# Simple_switch_scale.net
KiCad netlist of a schematic drawn in EAGLE
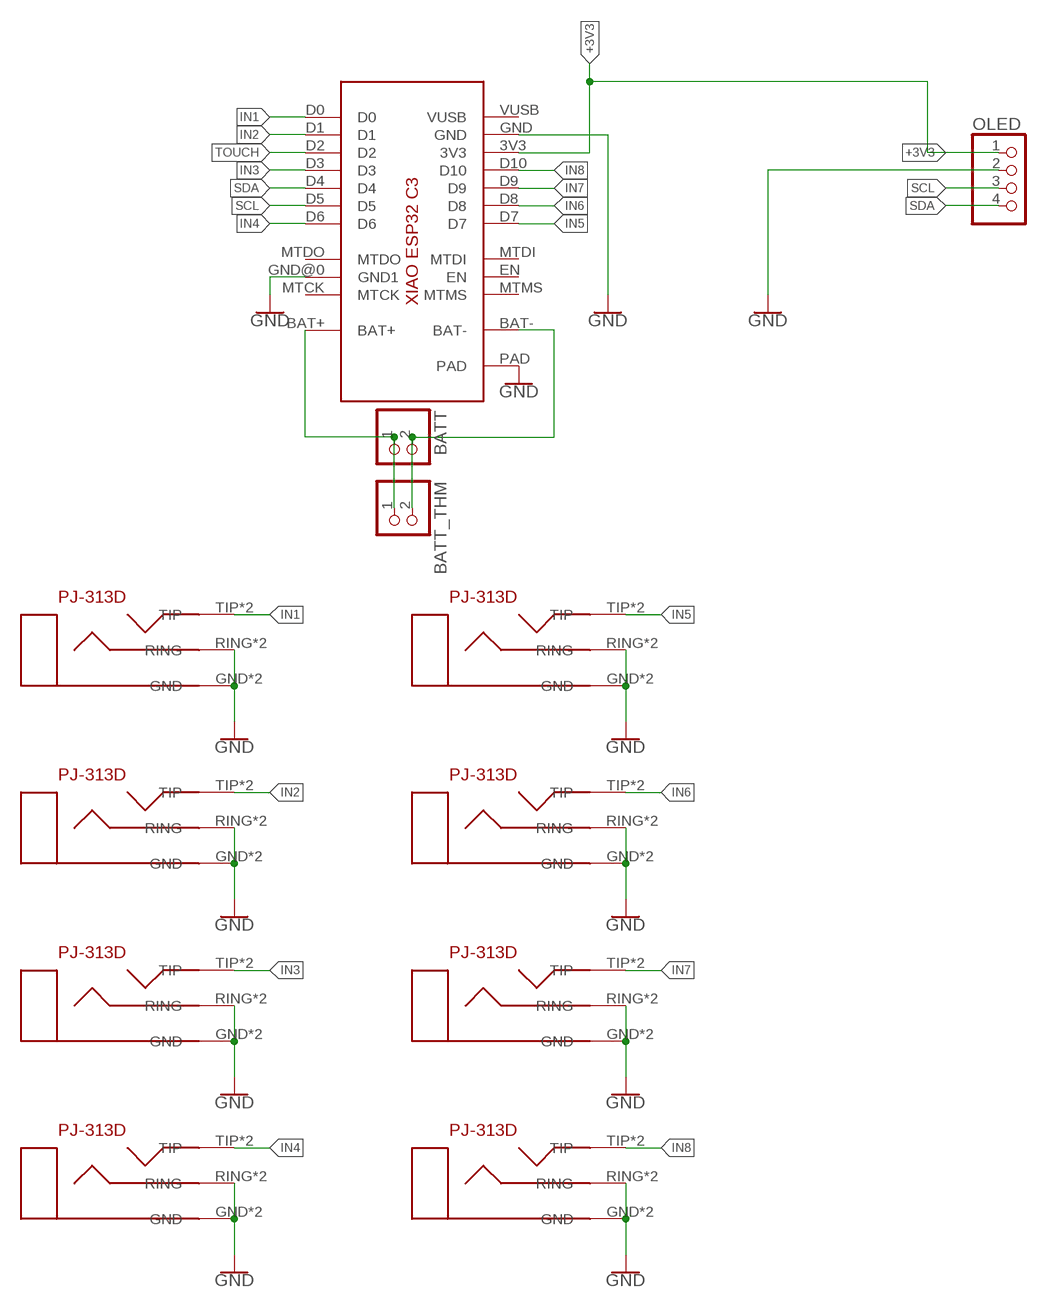
[diagram p0: schematic, sheet 1]

(export (version "E")
  (design (tool "Eeschema 10.0.6"))
  (components
    (comp (ref "BATT")
      (value "JST_2PIN-SMT-RA")
      (footprint "eagle-import:JST-PH-2-SMT-RA")
      (libsource (lib "eagle-import") (part "JST_2PIN-SMT-RA"))
    )
    (comp (ref "BATT_THM")
      (value "JST_2PIN-THM-RA")
      (footprint "eagle-import:JST-PH-2-THM-RA")
      (libsource (lib "eagle-import") (part "JST_2PIN-THM-RA"))
    )
    (comp (ref "IN1")
      (value "3.5MM_JACK")
      (footprint "eagle-import:PJ-313D-SMT")
      (libsource (lib "eagle-import") (part "3.5MM_JACK"))
    )
    (comp (ref "IN2")
      (value "3.5MM_JACK")
      (footprint "eagle-import:PJ-313D-SMT")
      (libsource (lib "eagle-import") (part "3.5MM_JACK"))
    )
    (comp (ref "IN3")
      (value "3.5MM_JACK")
      (footprint "eagle-import:PJ-313D-SMT")
      (libsource (lib "eagle-import") (part "3.5MM_JACK"))
    )
    (comp (ref "IN4")
      (value "3.5MM_JACK")
      (footprint "eagle-import:PJ-313D-SMT")
      (libsource (lib "eagle-import") (part "3.5MM_JACK"))
    )
    (comp (ref "IN5")
      (value "3.5MM_JACK")
      (footprint "eagle-import:PJ-313D-SMT")
      (libsource (lib "eagle-import") (part "3.5MM_JACK"))
    )
    (comp (ref "IN6")
      (value "3.5MM_JACK")
      (footprint "eagle-import:PJ-313D-SMT")
      (libsource (lib "eagle-import") (part "3.5MM_JACK"))
    )
    (comp (ref "IN7")
      (value "3.5MM_JACK")
      (footprint "eagle-import:PJ-313D-SMT")
      (libsource (lib "eagle-import") (part "3.5MM_JACK"))
    )
    (comp (ref "IN8")
      (value "3.5MM_JACK")
      (footprint "eagle-import:PJ-313D-SMT")
      (libsource (lib "eagle-import") (part "3.5MM_JACK"))
    )
    (comp (ref "OLED")
      (value "HEADER-1X4")
      (footprint "eagle-import:1X04_OVAL")
      (libsource (lib "eagle-import") (part "HEADER-1X4"))
    )
    (comp (ref "U$1")
      (value "XIAO_ESP32C3_SMD")
      (footprint "eagle-import:XIAO_ESP32C3_SMD")
      (libsource (lib "eagle-import") (part "XIAO_ESP32C3_SMD"))
    )
  )
  (nets
    (net (code "1") (name "+3V3") (class "Default")
      (node (ref "OLED") (pin "1") (pinfunction "1_1") (pintype "passive"))
      (node (ref "U$1") (pin "3V3") (pinfunction "3V3_3V3") (pintype "bidirectional"))
    )
    (net (code "2") (name "GND") (class "Default")
      (node (ref "IN1") (pin "GND") (pinfunction "GND_GND") (pintype "bidirectional"))
      (node (ref "IN1") (pin "GND0") (pinfunction "GND_GND0") (pintype "bidirectional"))
      (node (ref "IN1") (pin "RING") (pinfunction "RING_RING") (pintype "bidirectional"))
      (node (ref "IN1") (pin "RING0") (pinfunction "RING_RING0") (pintype "bidirectional"))
      (node (ref "IN2") (pin "GND") (pinfunction "GND_GND") (pintype "bidirectional"))
      (node (ref "IN2") (pin "GND0") (pinfunction "GND_GND0") (pintype "bidirectional"))
      (node (ref "IN2") (pin "RING") (pinfunction "RING_RING") (pintype "bidirectional"))
      (node (ref "IN2") (pin "RING0") (pinfunction "RING_RING0") (pintype "bidirectional"))
      (node (ref "IN3") (pin "GND") (pinfunction "GND_GND") (pintype "bidirectional"))
      (node (ref "IN3") (pin "GND0") (pinfunction "GND_GND0") (pintype "bidirectional"))
      (node (ref "IN3") (pin "RING") (pinfunction "RING_RING") (pintype "bidirectional"))
      (node (ref "IN3") (pin "RING0") (pinfunction "RING_RING0") (pintype "bidirectional"))
      (node (ref "IN4") (pin "GND") (pinfunction "GND_GND") (pintype "bidirectional"))
      (node (ref "IN4") (pin "GND0") (pinfunction "GND_GND0") (pintype "bidirectional"))
      (node (ref "IN4") (pin "RING") (pinfunction "RING_RING") (pintype "bidirectional"))
      (node (ref "IN4") (pin "RING0") (pinfunction "RING_RING0") (pintype "bidirectional"))
      (node (ref "IN5") (pin "GND") (pinfunction "GND_GND") (pintype "bidirectional"))
      (node (ref "IN5") (pin "GND0") (pinfunction "GND_GND0") (pintype "bidirectional"))
      (node (ref "IN5") (pin "RING") (pinfunction "RING_RING") (pintype "bidirectional"))
      (node (ref "IN5") (pin "RING0") (pinfunction "RING_RING0") (pintype "bidirectional"))
      (node (ref "IN6") (pin "GND") (pinfunction "GND_GND") (pintype "bidirectional"))
      (node (ref "IN6") (pin "GND0") (pinfunction "GND_GND0") (pintype "bidirectional"))
      (node (ref "IN6") (pin "RING") (pinfunction "RING_RING") (pintype "bidirectional"))
      (node (ref "IN6") (pin "RING0") (pinfunction "RING_RING0") (pintype "bidirectional"))
      (node (ref "IN7") (pin "GND") (pinfunction "GND_GND") (pintype "bidirectional"))
      (node (ref "IN7") (pin "GND0") (pinfunction "GND_GND0") (pintype "bidirectional"))
      (node (ref "IN7") (pin "RING") (pinfunction "RING_RING") (pintype "bidirectional"))
      (node (ref "IN7") (pin "RING0") (pinfunction "RING_RING0") (pintype "bidirectional"))
      (node (ref "IN8") (pin "GND") (pinfunction "GND_GND") (pintype "bidirectional"))
      (node (ref "IN8") (pin "GND0") (pinfunction "GND_GND0") (pintype "bidirectional"))
      (node (ref "IN8") (pin "RING") (pinfunction "RING_RING") (pintype "bidirectional"))
      (node (ref "IN8") (pin "RING0") (pinfunction "RING_RING0") (pintype "bidirectional"))
      (node (ref "OLED") (pin "2") (pinfunction "2_2") (pintype "passive"))
      (node (ref "U$1") (pin "GND") (pinfunction "GND_GND") (pintype "bidirectional"))
      (node (ref "U$1") (pin "GND@0") (pinfunction "GND1_GND@0") (pintype "bidirectional"))
      (node (ref "U$1") (pin "PAD") (pinfunction "PAD_PAD") (pintype "bidirectional"))
    )
    (net (code "3") (name "IN1") (class "Default")
      (node (ref "IN1") (pin "TIP") (pinfunction "TIP_TIP") (pintype "bidirectional"))
      (node (ref "IN1") (pin "TIP0") (pinfunction "TIP_TIP0") (pintype "bidirectional"))
      (node (ref "U$1") (pin "D0") (pinfunction "D0_D0") (pintype "bidirectional"))
    )
    (net (code "4") (name "IN2") (class "Default")
      (node (ref "IN2") (pin "TIP") (pinfunction "TIP_TIP") (pintype "bidirectional"))
      (node (ref "IN2") (pin "TIP0") (pinfunction "TIP_TIP0") (pintype "bidirectional"))
      (node (ref "U$1") (pin "D1") (pinfunction "D1_D1") (pintype "bidirectional"))
    )
    (net (code "5") (name "IN3") (class "Default")
      (node (ref "IN3") (pin "TIP") (pinfunction "TIP_TIP") (pintype "bidirectional"))
      (node (ref "IN3") (pin "TIP0") (pinfunction "TIP_TIP0") (pintype "bidirectional"))
      (node (ref "U$1") (pin "D3") (pinfunction "D3_D3") (pintype "bidirectional"))
    )
    (net (code "6") (name "IN4") (class "Default")
      (node (ref "IN4") (pin "TIP") (pinfunction "TIP_TIP") (pintype "bidirectional"))
      (node (ref "IN4") (pin "TIP0") (pinfunction "TIP_TIP0") (pintype "bidirectional"))
      (node (ref "U$1") (pin "D6") (pinfunction "D6_D6") (pintype "bidirectional"))
    )
    (net (code "7") (name "IN5") (class "Default")
      (node (ref "IN5") (pin "TIP") (pinfunction "TIP_TIP") (pintype "bidirectional"))
      (node (ref "IN5") (pin "TIP0") (pinfunction "TIP_TIP0") (pintype "bidirectional"))
      (node (ref "U$1") (pin "D7") (pinfunction "D7_D7") (pintype "bidirectional"))
    )
    (net (code "8") (name "IN6") (class "Default")
      (node (ref "IN6") (pin "TIP") (pinfunction "TIP_TIP") (pintype "bidirectional"))
      (node (ref "IN6") (pin "TIP0") (pinfunction "TIP_TIP0") (pintype "bidirectional"))
      (node (ref "U$1") (pin "D8") (pinfunction "D8_D8") (pintype "bidirectional"))
    )
    (net (code "9") (name "IN7") (class "Default")
      (node (ref "IN7") (pin "TIP") (pinfunction "TIP_TIP") (pintype "bidirectional"))
      (node (ref "IN7") (pin "TIP0") (pinfunction "TIP_TIP0") (pintype "bidirectional"))
      (node (ref "U$1") (pin "D9") (pinfunction "D9_D9") (pintype "bidirectional"))
    )
    (net (code "10") (name "IN8") (class "Default")
      (node (ref "IN8") (pin "TIP") (pinfunction "TIP_TIP") (pintype "bidirectional"))
      (node (ref "IN8") (pin "TIP0") (pinfunction "TIP_TIP0") (pintype "bidirectional"))
      (node (ref "U$1") (pin "D10") (pinfunction "D10_D10") (pintype "bidirectional"))
    )
    (net (code "11") (name "Net-(BATT-1)") (class "Default")
      (node (ref "BATT") (pin "2") (pinfunction "1_2") (pintype "passive"))
      (node (ref "BATT_THM") (pin "2") (pinfunction "1_2") (pintype "passive"))
      (node (ref "U$1") (pin "BAT-") (pinfunction "BAT-_BAT-") (pintype "bidirectional"))
    )
    (net (code "12") (name "Net-(BATT-2)") (class "Default")
      (node (ref "BATT") (pin "1") (pinfunction "2_1") (pintype "passive"))
      (node (ref "BATT_THM") (pin "1") (pinfunction "2_1") (pintype "passive"))
      (node (ref "U$1") (pin "BAT+") (pinfunction "BAT+_BAT+") (pintype "bidirectional"))
    )
    (net (code "13") (name "SCL") (class "Default")
      (node (ref "OLED") (pin "3") (pinfunction "3_3") (pintype "passive"))
      (node (ref "U$1") (pin "D5") (pinfunction "D5_D5") (pintype "bidirectional"))
    )
    (net (code "14") (name "SDA") (class "Default")
      (node (ref "OLED") (pin "4") (pinfunction "4_4") (pintype "passive"))
      (node (ref "U$1") (pin "D4") (pinfunction "D4_D4") (pintype "bidirectional"))
    )
    (net (code "15") (name "TOUCH") (class "Default")
      (node (ref "U$1") (pin "D2") (pinfunction "D2_D2") (pintype "bidirectional"))
    )
    (net (code "16") (name "unconnected-(U$1-PadEN)") (class "Default")
      (node (ref "U$1") (pin "EN") (pinfunction "EN_EN") (pintype "bidirectional"))
    )
    (net (code "17") (name "unconnected-(U$1-PadMTCK)") (class "Default")
      (node (ref "U$1") (pin "MTCK") (pinfunction "MTCK_MTCK") (pintype "bidirectional"))
    )
    (net (code "18") (name "unconnected-(U$1-PadMTDI)") (class "Default")
      (node (ref "U$1") (pin "MTDI") (pinfunction "MTDI_MTDI") (pintype "bidirectional"))
    )
    (net (code "19") (name "unconnected-(U$1-PadMTDO)") (class "Default")
      (node (ref "U$1") (pin "MTDO") (pinfunction "MTDO_MTDO") (pintype "bidirectional"))
    )
    (net (code "20") (name "unconnected-(U$1-PadMTMS)") (class "Default")
      (node (ref "U$1") (pin "MTMS") (pinfunction "MTMS_MTMS") (pintype "bidirectional"))
    )
    (net (code "21") (name "unconnected-(U$1-PadVUSB)") (class "Default")
      (node (ref "U$1") (pin "VUSB") (pinfunction "VUSB_VUSB") (pintype "bidirectional"))
    )
  )
)
